# Encoder_Input.net
KiCad netlist of a schematic drawn in Altium Designer
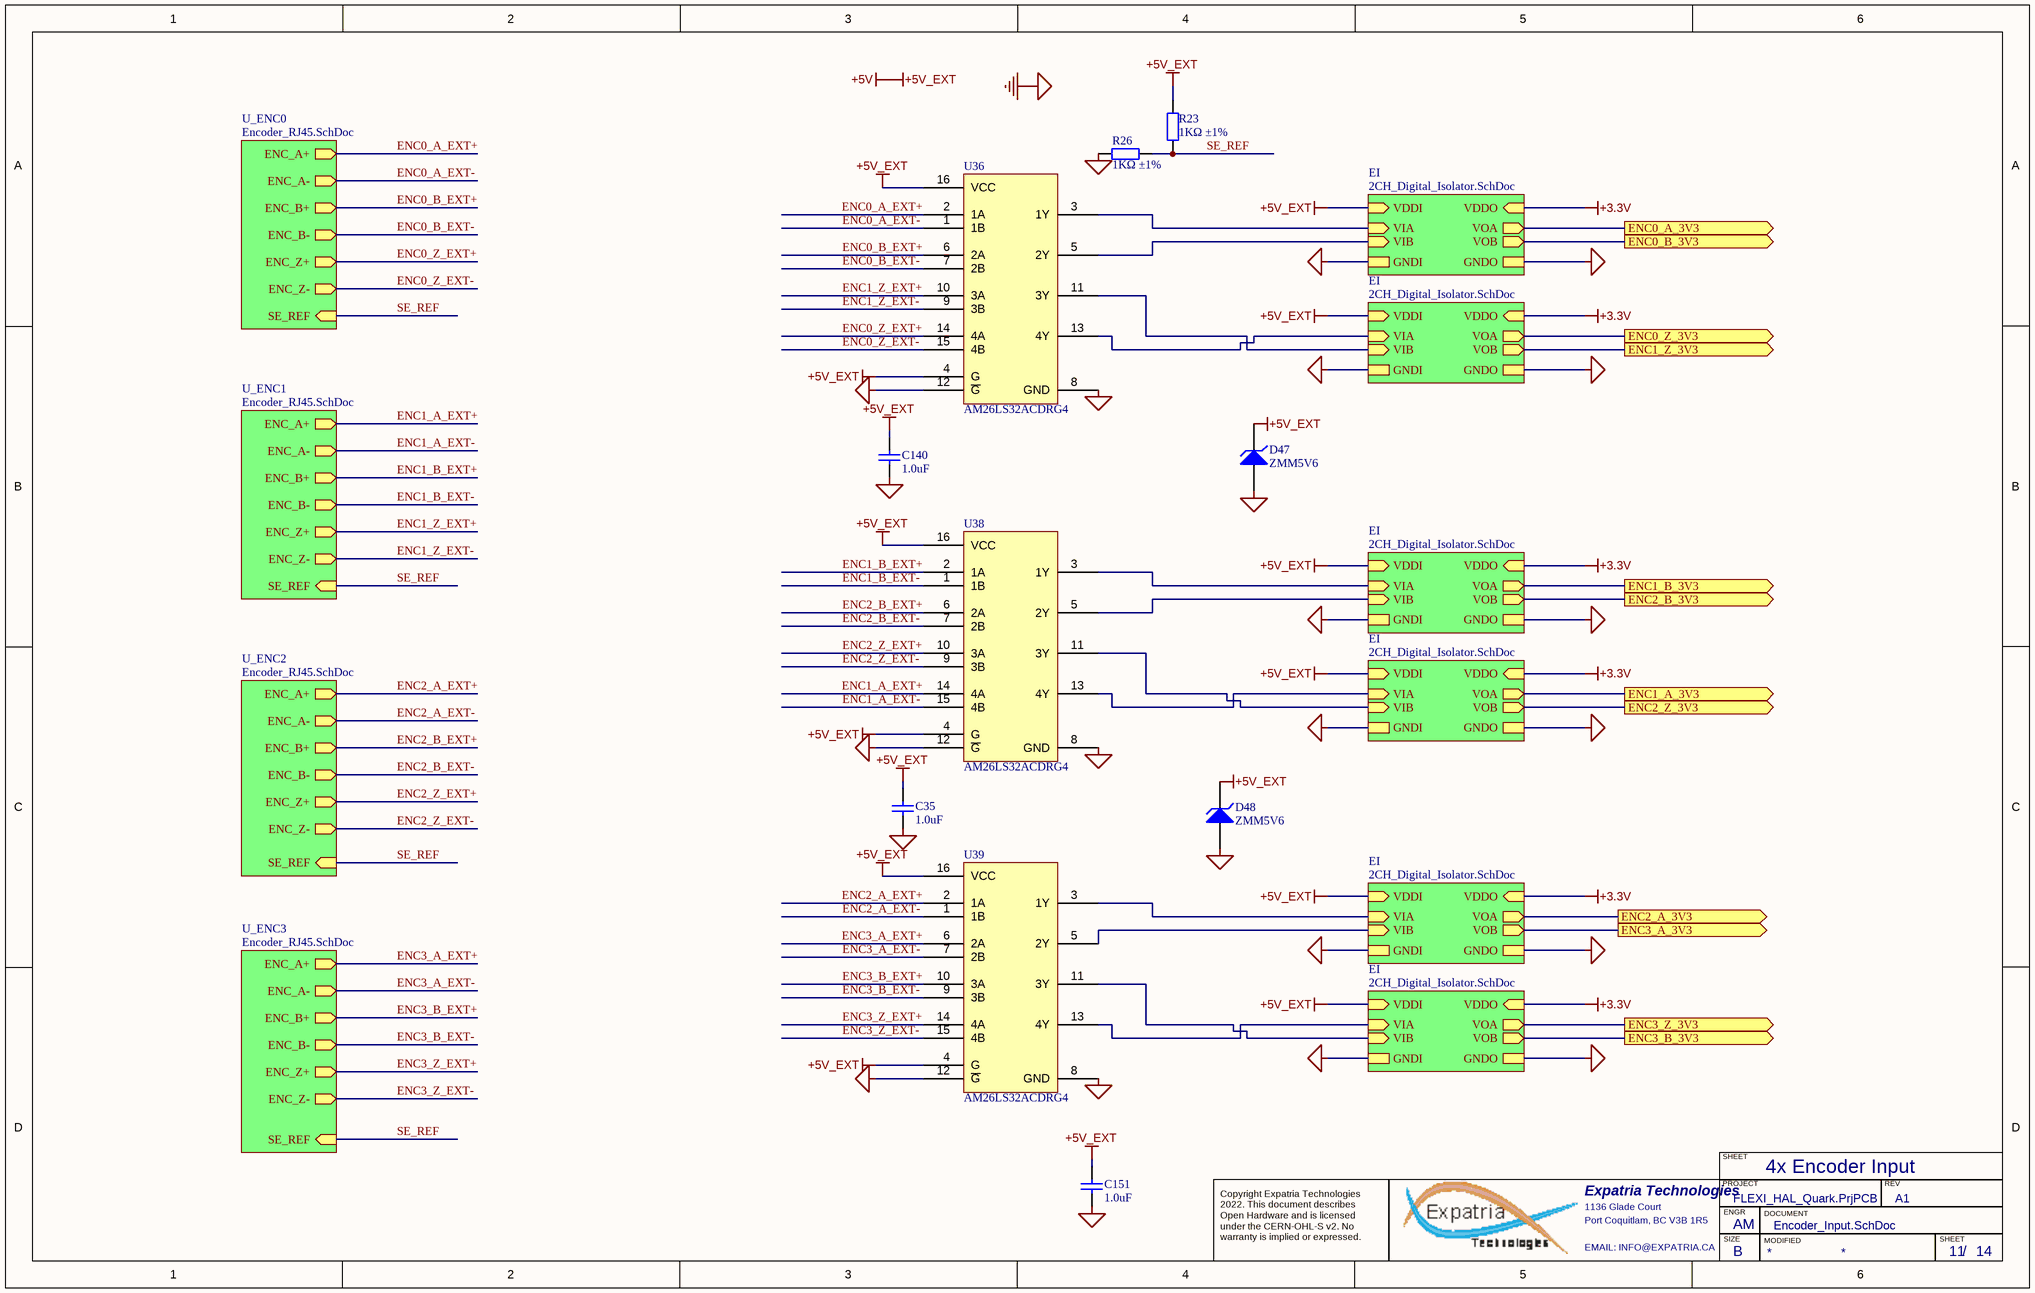
[diagram p0: Encoder_Input.SchDoc]

(export (version "E")
  (design (tool "Eeschema 10.0.6"))
  (components
    (comp (ref "C35")
      (value "1.0uF")
      (footprint "0402_C")
      (description "Chip capacitor")
      (fields
        (field (name "MANUFACTURER") "Samsung Electro-Mechanics")
        (field (name "PARTNUMBER") "CL05A105KA5NQNC")
      )
      (libsource (lib "Cap") (part "0402 1.0uF (105) 10% 25V"))
    )
    (comp (ref "C140")
      (value "1.0uF")
      (footprint "0402_C")
      (description "Chip capacitor")
      (fields
        (field (name "MANUFACTURER") "Samsung Electro-Mechanics")
        (field (name "PARTNUMBER") "CL05A105KA5NQNC")
      )
      (libsource (lib "Cap") (part "0402 1.0uF (105) 10% 25V"))
    )
    (comp (ref "C151")
      (value "1.0uF")
      (footprint "0402_C")
      (description "Chip capacitor")
      (fields
        (field (name "MANUFACTURER") "Samsung Electro-Mechanics")
        (field (name "PARTNUMBER") "CL05A105KA5NQNC")
      )
      (libsource (lib "Cap") (part "0402 1.0uF (105) 10% 25V"))
    )
    (comp (ref "D47")
      (value "ZMM5V6")
      (footprint "LL-34")
      (description "500mW - 0.1uA @ 1V 5.6V LL-34 Zener Diodes ROHS")
      (libsource (lib "Zener") (part "LL-34 ZMM5V6"))
    )
    (comp (ref "D48")
      (value "ZMM5V6")
      (footprint "LL-34")
      (description "500mW - 0.1uA @ 1V 5.6V LL-34 Zener Diodes ROHS")
      (libsource (lib "Zener") (part "LL-34 ZMM5V6"))
    )
    (comp (ref "R23")
      (value "1KΩ ±1%")
      (footprint "0402_R")
      (description "Chip resistor")
      (fields (field (name "MANUFACTURER") "Uniroyal Elec") (field (name "PARTNUMBER") "0402WGF1001TCE"))
      (libsource (lib "") (part "0402 1K (1001) 1%_1"))
    )
    (comp (ref "R26")
      (value "1KΩ ±1%")
      (footprint "0402_R")
      (description "Chip resistor")
      (fields (field (name "MANUFACTURER") "Uniroyal Elec") (field (name "PARTNUMBER") "0402WGF1001TCE"))
      (libsource (lib "RES") (part "0402 1K (1001) 1%"))
    )
    (comp (ref "U36")
      (value "AM26LS32ACDRG4")
      (footprint "SOIC-16_150mil")
      (description "RS-422 Interface IC Quad Diff Line Rcvr")
      (libsource (lib "IC") (part "AM26LS32ACDRG4_[C6180]"))
    )
    (comp (ref "U38")
      (value "AM26LS32ACDRG4")
      (footprint "SOIC-16_150mil")
      (description "RS-422 Interface IC Quad Diff Line Rcvr")
      (libsource (lib "IC") (part "AM26LS32ACDRG4_[C6180]"))
    )
    (comp (ref "U39")
      (value "AM26LS32ACDRG4")
      (footprint "SOIC-16_150mil")
      (description "RS-422 Interface IC Quad Diff Line Rcvr")
      (libsource (lib "IC") (part "AM26LS32ACDRG4_[C6180]"))
    )
  )
  (nets
    (net (code "2") (name "+5V") (class "Default")
      (node (ref "C140") (pin "2") (pinfunction "2_2") (pintype "passive"))
      (node (ref "C151") (pin "2") (pinfunction "2_2") (pintype "passive"))
      (node (ref "C35") (pin "2") (pinfunction "2_2") (pintype "passive"))
      (node (ref "D47") (pin "2") (pinfunction "K_2") (pintype "passive"))
      (node (ref "D48") (pin "2") (pinfunction "K_2") (pintype "passive"))
      (node (ref "R23") (pin "1") (pinfunction "1_1") (pintype "passive"))
      (node (ref "U36") (pin "16") (pinfunction "VCC_16") (pintype "passive"))
      (node (ref "U36") (pin "4") (pinfunction "G_4") (pintype "passive"))
      (node (ref "U38") (pin "16") (pinfunction "VCC_16") (pintype "passive"))
      (node (ref "U38") (pin "4") (pinfunction "G_4") (pintype "passive"))
      (node (ref "U39") (pin "16") (pinfunction "VCC_16") (pintype "passive"))
      (node (ref "U39") (pin "4") (pinfunction "G_4") (pintype "passive"))
    )
    (net (code "4") (name "/ENC0_A_EXT+") (class "Default")
      (node (ref "U36") (pin "2") (pinfunction "1A_2") (pintype "passive"))
    )
    (net (code "5") (name "/ENC0_A_EXT-") (class "Default")
      (node (ref "U36") (pin "1") (pinfunction "1B_1") (pintype "passive"))
    )
    (net (code "7") (name "/ENC0_B_EXT+") (class "Default")
      (node (ref "U36") (pin "6") (pinfunction "2A_6") (pintype "passive"))
    )
    (net (code "8") (name "/ENC0_B_EXT-") (class "Default")
      (node (ref "U36") (pin "7") (pinfunction "2B_7") (pintype "passive"))
    )
    (net (code "10") (name "/ENC0_Z_EXT+") (class "Default")
      (node (ref "U36") (pin "14") (pinfunction "4A_14") (pintype "passive"))
    )
    (net (code "11") (name "/ENC0_Z_EXT-") (class "Default")
      (node (ref "U36") (pin "15") (pinfunction "4B_15") (pintype "passive"))
    )
    (net (code "13") (name "/ENC1_A_EXT+") (class "Default")
      (node (ref "U38") (pin "14") (pinfunction "4A_14") (pintype "passive"))
    )
    (net (code "14") (name "/ENC1_A_EXT-") (class "Default")
      (node (ref "U38") (pin "15") (pinfunction "4B_15") (pintype "passive"))
    )
    (net (code "16") (name "/ENC1_B_EXT+") (class "Default")
      (node (ref "U38") (pin "2") (pinfunction "1A_2") (pintype "passive"))
    )
    (net (code "17") (name "/ENC1_B_EXT-") (class "Default")
      (node (ref "U38") (pin "1") (pinfunction "1B_1") (pintype "passive"))
    )
    (net (code "19") (name "/ENC1_Z_EXT+") (class "Default")
      (node (ref "U36") (pin "10") (pinfunction "3A_10") (pintype "passive"))
    )
    (net (code "20") (name "/ENC1_Z_EXT-") (class "Default")
      (node (ref "U36") (pin "9") (pinfunction "3B_9") (pintype "passive"))
    )
    (net (code "22") (name "/ENC2_A_EXT+") (class "Default")
      (node (ref "U39") (pin "2") (pinfunction "1A_2") (pintype "passive"))
    )
    (net (code "23") (name "/ENC2_A_EXT-") (class "Default")
      (node (ref "U39") (pin "1") (pinfunction "1B_1") (pintype "passive"))
    )
    (net (code "25") (name "/ENC2_B_EXT+") (class "Default")
      (node (ref "U38") (pin "6") (pinfunction "2A_6") (pintype "passive"))
    )
    (net (code "26") (name "/ENC2_B_EXT-") (class "Default")
      (node (ref "U38") (pin "7") (pinfunction "2B_7") (pintype "passive"))
    )
    (net (code "28") (name "/ENC2_Z_EXT+") (class "Default")
      (node (ref "U38") (pin "10") (pinfunction "3A_10") (pintype "passive"))
    )
    (net (code "29") (name "/ENC2_Z_EXT-") (class "Default")
      (node (ref "U38") (pin "9") (pinfunction "3B_9") (pintype "passive"))
    )
    (net (code "31") (name "/ENC3_A_EXT+") (class "Default")
      (node (ref "U39") (pin "6") (pinfunction "2A_6") (pintype "passive"))
    )
    (net (code "32") (name "/ENC3_A_EXT-") (class "Default")
      (node (ref "U39") (pin "7") (pinfunction "2B_7") (pintype "passive"))
    )
    (net (code "34") (name "/ENC3_B_EXT+") (class "Default")
      (node (ref "U39") (pin "10") (pinfunction "3A_10") (pintype "passive"))
    )
    (net (code "35") (name "/ENC3_B_EXT-") (class "Default")
      (node (ref "U39") (pin "9") (pinfunction "3B_9") (pintype "passive"))
    )
    (net (code "37") (name "/ENC3_Z_EXT+") (class "Default")
      (node (ref "U39") (pin "14") (pinfunction "4A_14") (pintype "passive"))
    )
    (net (code "38") (name "/ENC3_Z_EXT-") (class "Default")
      (node (ref "U39") (pin "15") (pinfunction "4B_15") (pintype "passive"))
    )
    (net (code "39") (name "/SE_REF") (class "Default")
      (node (ref "R23") (pin "2") (pinfunction "2_2") (pintype "passive"))
      (node (ref "R26") (pin "2") (pinfunction "2_2") (pintype "passive"))
    )
    (net (code "40") (name "/VIA") (class "Default")
      (node (ref "U38") (pin "3") (pinfunction "1Y_3") (pintype "passive"))
    )
    (net (code "41") (name "/VIA_1") (class "Default")
      (node (ref "U39") (pin "3") (pinfunction "1Y_3") (pintype "passive"))
    )
    (net (code "42") (name "/VIA_2") (class "Default")
      (node (ref "U39") (pin "13") (pinfunction "4Y_13") (pintype "passive"))
    )
    (net (code "43") (name "/VIA_3") (class "Default")
      (node (ref "U36") (pin "13") (pinfunction "4Y_13") (pintype "passive"))
    )
    (net (code "44") (name "/VIA_4") (class "Default")
      (node (ref "U36") (pin "3") (pinfunction "1Y_3") (pintype "passive"))
    )
    (net (code "45") (name "/VIA_5") (class "Default")
      (node (ref "U38") (pin "13") (pinfunction "4Y_13") (pintype "passive"))
    )
    (net (code "46") (name "/VIB") (class "Default")
      (node (ref "U38") (pin "11") (pinfunction "3Y_11") (pintype "passive"))
    )
    (net (code "47") (name "/VIB_1") (class "Default")
      (node (ref "U39") (pin "5") (pinfunction "2Y_5") (pintype "passive"))
    )
    (net (code "48") (name "/VIB_2") (class "Default")
      (node (ref "U39") (pin "11") (pinfunction "3Y_11") (pintype "passive"))
    )
    (net (code "49") (name "/VIB_3") (class "Default")
      (node (ref "U36") (pin "11") (pinfunction "3Y_11") (pintype "passive"))
    )
    (net (code "50") (name "/VIB_4") (class "Default")
      (node (ref "U36") (pin "5") (pinfunction "2Y_5") (pintype "passive"))
    )
    (net (code "51") (name "/VIB_5") (class "Default")
      (node (ref "U38") (pin "5") (pinfunction "2Y_5") (pintype "passive"))
    )
    (net (code "52") (name "GND") (class "Default")
      (node (ref "C140") (pin "1") (pinfunction "1_1") (pintype "passive"))
      (node (ref "C151") (pin "1") (pinfunction "1_1") (pintype "passive"))
      (node (ref "C35") (pin "1") (pinfunction "1_1") (pintype "passive"))
      (node (ref "D47") (pin "1") (pinfunction "A_1") (pintype "passive"))
      (node (ref "D48") (pin "1") (pinfunction "A_1") (pintype "passive"))
      (node (ref "R26") (pin "1") (pinfunction "1_1") (pintype "passive"))
      (node (ref "U36") (pin "12") (pinfunction "~{G}_12") (pintype "passive"))
      (node (ref "U36") (pin "8") (pinfunction "GND_8") (pintype "passive"))
      (node (ref "U38") (pin "12") (pinfunction "~{G}_12") (pintype "passive"))
      (node (ref "U38") (pin "8") (pinfunction "GND_8") (pintype "passive"))
      (node (ref "U39") (pin "12") (pinfunction "~{G}_12") (pintype "passive"))
      (node (ref "U39") (pin "8") (pinfunction "GND_8") (pintype "passive"))
    )
  )
)
